# kijelz.net
KiCad netlist of a schematic drawn in EAGLE
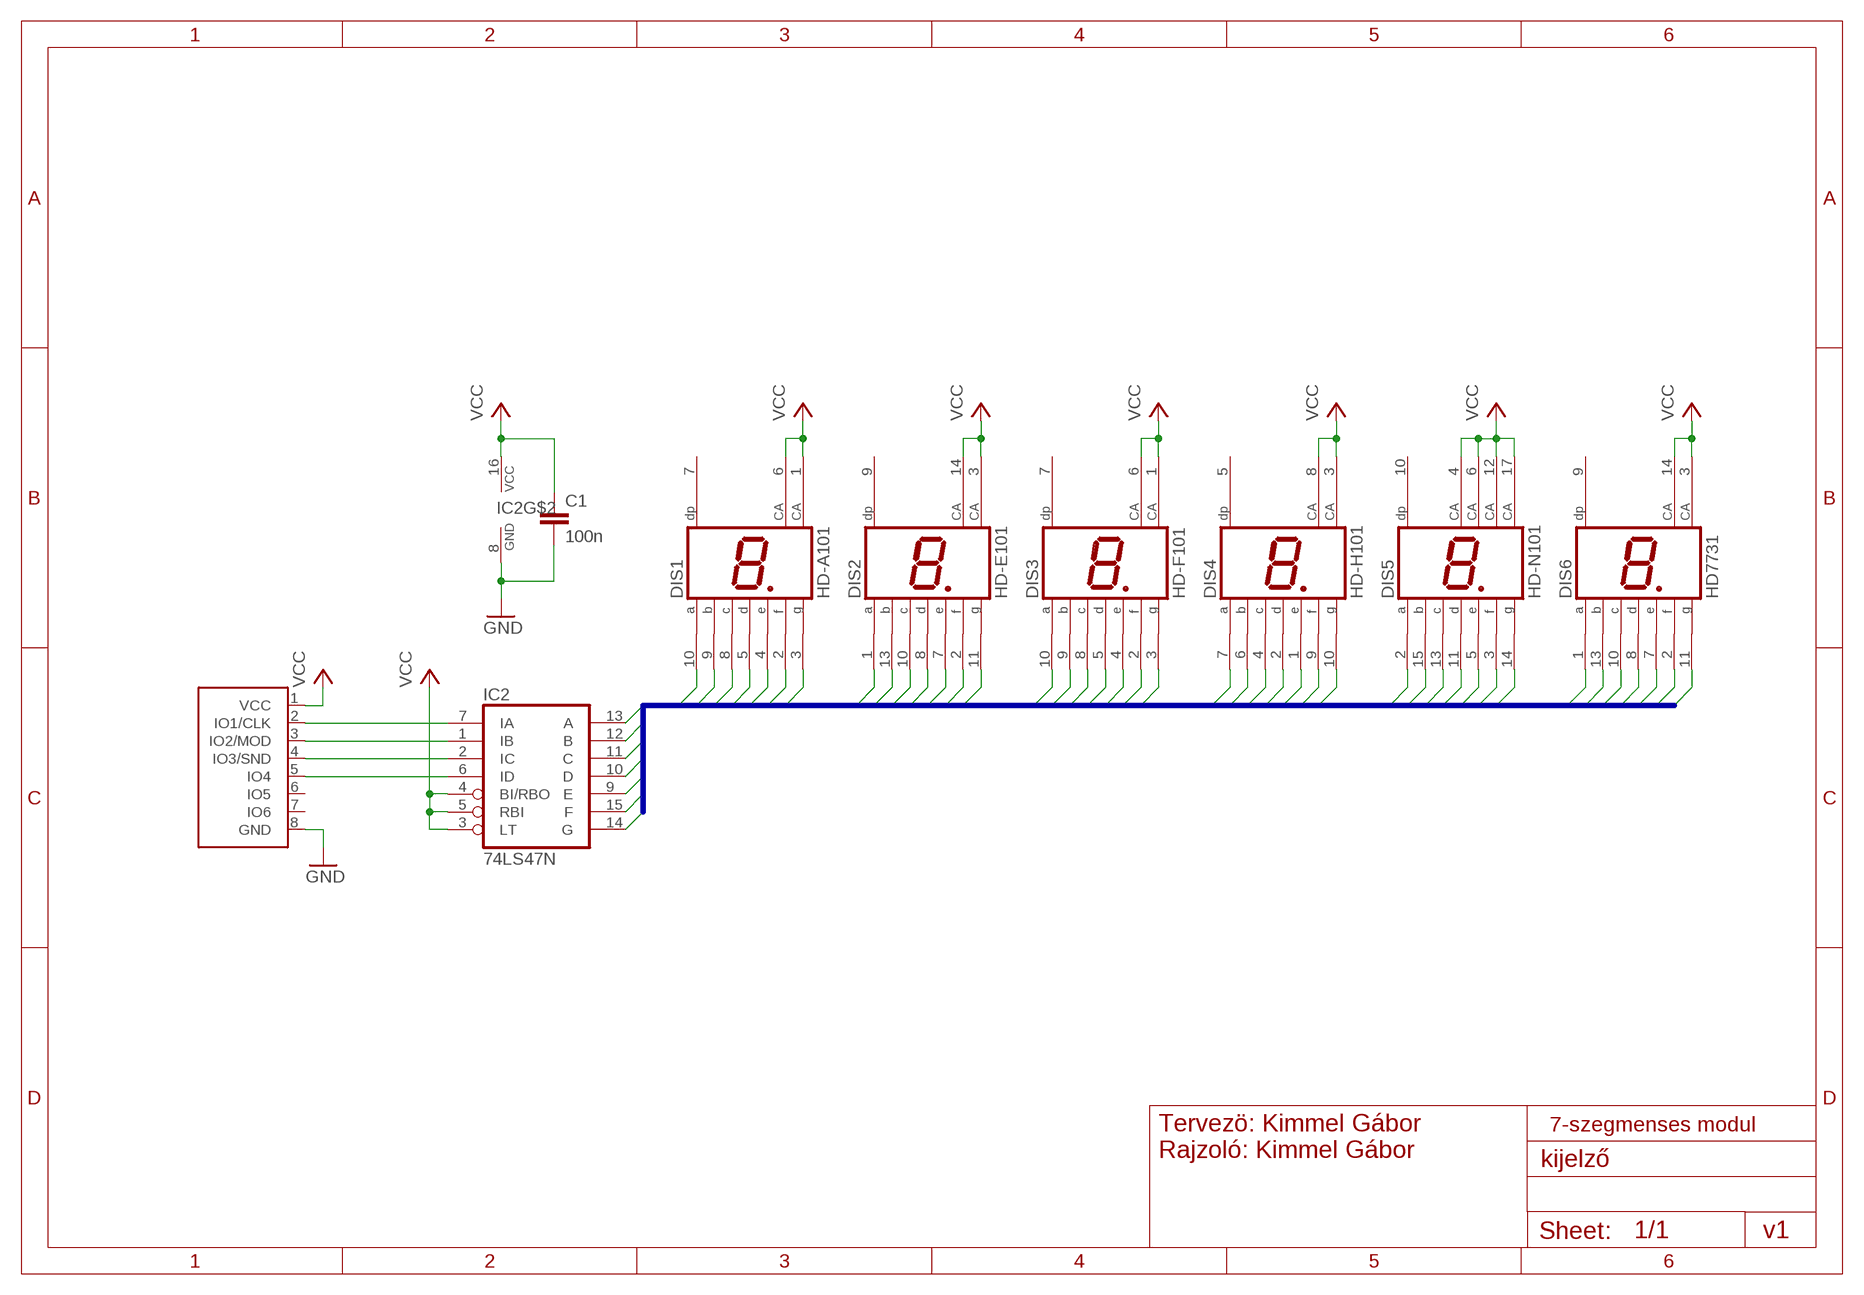
[diagram p0: schematic, sheet 1]

(export (version "E")
  (design (tool "Eeschema 10.0.6"))
  (components
    (comp (ref "C1")
      (value "100n")
      (footprint "eagle-import:C075-032X103")
      (libsource (lib "eagle-import") (part "C-EU075-032X103"))
    )
    (comp (ref "DIS1")
      (value "HD-A101")
      (footprint "eagle-import:HDSP-A")
      (libsource (lib "eagle-import") (part "HD-A101"))
    )
    (comp (ref "DIS2")
      (value "HD-E101")
      (footprint "eagle-import:HDSP-I")
      (libsource (lib "eagle-import") (part "HD-E101"))
    )
    (comp (ref "DIS3")
      (value "HD-F101")
      (footprint "eagle-import:HDSP-E")
      (libsource (lib "eagle-import") (part "HD-F101"))
    )
    (comp (ref "DIS4")
      (value "HD-H101")
      (footprint "eagle-import:HDSP-M")
      (libsource (lib "eagle-import") (part "HD-H101"))
    )
    (comp (ref "DIS5")
      (value "HD-N101")
      (footprint "eagle-import:HDSP-Q")
      (libsource (lib "eagle-import") (part "HD-N101"))
    )
    (comp (ref "DIS6")
      (value "HD7731")
      (footprint "eagle-import:HD7730")
      (libsource (lib "eagle-import") (part "HD7731"))
    )
    (comp (ref "IC2")
      (value "74LS47N")
      (footprint "eagle-import:DIL16")
      (libsource (lib "eagle-import") (part "7447NLS"))
    )
    (comp (ref "U$1")
      (value "GANZ-CONNECTOR")
      (footprint "eagle-import:FE08W")
      (libsource (lib "eagle-import") (part "GANZ-CONNECTOR"))
    )
  )
  (nets
    (net (code "1") (name "/A") (class "Default")
      (node (ref "DIS1") (pin "10") (pinfunction "A_10") (pintype "passive"))
      (node (ref "DIS2") (pin "1") (pinfunction "A_1") (pintype "passive"))
      (node (ref "DIS3") (pin "10") (pinfunction "A_10") (pintype "passive"))
      (node (ref "DIS4") (pin "7") (pinfunction "A_7") (pintype "passive"))
      (node (ref "DIS5") (pin "2") (pinfunction "A_2") (pintype "passive"))
      (node (ref "DIS6") (pin "1") (pinfunction "A_1") (pintype "passive"))
      (node (ref "IC2") (pin "13") (pinfunction "A_13") (pintype "output"))
    )
    (net (code "2") (name "/B") (class "Default")
      (node (ref "DIS1") (pin "9") (pinfunction "B_9") (pintype "passive"))
      (node (ref "DIS2") (pin "13") (pinfunction "B_13") (pintype "passive"))
      (node (ref "DIS3") (pin "9") (pinfunction "B_9") (pintype "passive"))
      (node (ref "DIS4") (pin "6") (pinfunction "B_6") (pintype "passive"))
      (node (ref "DIS5") (pin "15") (pinfunction "B_15") (pintype "passive"))
      (node (ref "DIS6") (pin "13") (pinfunction "B_13") (pintype "passive"))
      (node (ref "IC2") (pin "12") (pinfunction "B_12") (pintype "output"))
    )
    (net (code "3") (name "/C") (class "Default")
      (node (ref "DIS1") (pin "8") (pinfunction "C_8") (pintype "passive"))
      (node (ref "DIS2") (pin "10") (pinfunction "C_10") (pintype "passive"))
      (node (ref "DIS3") (pin "8") (pinfunction "C_8") (pintype "passive"))
      (node (ref "DIS4") (pin "4") (pinfunction "C_4") (pintype "passive"))
      (node (ref "DIS5") (pin "13") (pinfunction "C_13") (pintype "passive"))
      (node (ref "DIS6") (pin "10") (pinfunction "C_10") (pintype "passive"))
      (node (ref "IC2") (pin "11") (pinfunction "C_11") (pintype "output"))
    )
    (net (code "4") (name "/D") (class "Default")
      (node (ref "DIS1") (pin "5") (pinfunction "D_5") (pintype "passive"))
      (node (ref "DIS2") (pin "8") (pinfunction "D_8") (pintype "passive"))
      (node (ref "DIS3") (pin "5") (pinfunction "D_5") (pintype "passive"))
      (node (ref "DIS4") (pin "2") (pinfunction "D_2") (pintype "passive"))
      (node (ref "DIS5") (pin "11") (pinfunction "D_11") (pintype "passive"))
      (node (ref "DIS6") (pin "8") (pinfunction "D_8") (pintype "passive"))
      (node (ref "IC2") (pin "10") (pinfunction "D_10") (pintype "output"))
    )
    (net (code "5") (name "/E") (class "Default")
      (node (ref "DIS1") (pin "4") (pinfunction "E_4") (pintype "passive"))
      (node (ref "DIS2") (pin "7") (pinfunction "E_7") (pintype "passive"))
      (node (ref "DIS3") (pin "4") (pinfunction "E_4") (pintype "passive"))
      (node (ref "DIS4") (pin "1") (pinfunction "E_1") (pintype "passive"))
      (node (ref "DIS5") (pin "5") (pinfunction "E_5") (pintype "passive"))
      (node (ref "DIS6") (pin "7") (pinfunction "E_7") (pintype "passive"))
      (node (ref "IC2") (pin "9") (pinfunction "E_9") (pintype "output"))
    )
    (net (code "6") (name "/F") (class "Default")
      (node (ref "DIS1") (pin "2") (pinfunction "F_2") (pintype "passive"))
      (node (ref "DIS2") (pin "2") (pinfunction "F_2") (pintype "passive"))
      (node (ref "DIS3") (pin "2") (pinfunction "F_2") (pintype "passive"))
      (node (ref "DIS4") (pin "9") (pinfunction "F_9") (pintype "passive"))
      (node (ref "DIS5") (pin "3") (pinfunction "F_3") (pintype "passive"))
      (node (ref "DIS6") (pin "2") (pinfunction "F_2") (pintype "passive"))
      (node (ref "IC2") (pin "15") (pinfunction "F_15") (pintype "output"))
    )
    (net (code "7") (name "/G") (class "Default")
      (node (ref "DIS1") (pin "3") (pinfunction "G_3") (pintype "passive"))
      (node (ref "DIS2") (pin "11") (pinfunction "G_11") (pintype "passive"))
      (node (ref "DIS3") (pin "3") (pinfunction "G_3") (pintype "passive"))
      (node (ref "DIS4") (pin "10") (pinfunction "G_10") (pintype "passive"))
      (node (ref "DIS5") (pin "14") (pinfunction "G_14") (pintype "passive"))
      (node (ref "DIS6") (pin "11") (pinfunction "G_11") (pintype "passive"))
      (node (ref "IC2") (pin "14") (pinfunction "G_14") (pintype "output"))
    )
    (net (code "8") (name "GND") (class "Default")
      (node (ref "C1") (pin "2") (pinfunction "2_2") (pintype "passive"))
      (node (ref "IC2") (pin "8") (pinfunction "GND_8") (pintype "power_in"))
      (node (ref "U$1") (pin "8") (pinfunction "GND_8") (pintype "bidirectional"))
    )
    (net (code "9") (name "Net-(IC2A-IA)") (class "Default")
      (node (ref "IC2") (pin "7") (pinfunction "IA_7") (pintype "input"))
      (node (ref "U$1") (pin "2") (pinfunction "IO1/CLK_2") (pintype "bidirectional"))
    )
    (net (code "10") (name "Net-(IC2A-IB)") (class "Default")
      (node (ref "IC2") (pin "1") (pinfunction "IB_1") (pintype "input"))
      (node (ref "U$1") (pin "3") (pinfunction "IO2/MOD_3") (pintype "bidirectional"))
    )
    (net (code "11") (name "Net-(IC2A-IC)") (class "Default")
      (node (ref "IC2") (pin "2") (pinfunction "IC_2") (pintype "input"))
      (node (ref "U$1") (pin "4") (pinfunction "IO3/SND_4") (pintype "bidirectional"))
    )
    (net (code "12") (name "Net-(IC2A-ID)") (class "Default")
      (node (ref "IC2") (pin "6") (pinfunction "ID_6") (pintype "input"))
      (node (ref "U$1") (pin "5") (pinfunction "IO4_5") (pintype "bidirectional"))
    )
    (net (code "13") (name "VCC") (class "Default")
      (node (ref "C1") (pin "1") (pinfunction "1_1") (pintype "passive"))
      (node (ref "DIS1") (pin "1") (pinfunction "CA_1") (pintype "passive"))
      (node (ref "DIS1") (pin "6") (pinfunction "CA_6") (pintype "passive"))
      (node (ref "DIS2") (pin "14") (pinfunction "CA_14") (pintype "passive"))
      (node (ref "DIS2") (pin "3") (pinfunction "CA_3") (pintype "passive"))
      (node (ref "DIS3") (pin "1") (pinfunction "CA_1") (pintype "passive"))
      (node (ref "DIS3") (pin "6") (pinfunction "CA_6") (pintype "passive"))
      (node (ref "DIS4") (pin "3") (pinfunction "CA_3") (pintype "passive"))
      (node (ref "DIS4") (pin "8") (pinfunction "CA_8") (pintype "passive"))
      (node (ref "DIS5") (pin "12") (pinfunction "CA_12") (pintype "passive"))
      (node (ref "DIS5") (pin "17") (pinfunction "CA_17") (pintype "passive"))
      (node (ref "DIS5") (pin "4") (pinfunction "CA_4") (pintype "passive"))
      (node (ref "DIS5") (pin "6") (pinfunction "CA_6") (pintype "passive"))
      (node (ref "DIS6") (pin "14") (pinfunction "CA_14") (pintype "passive"))
      (node (ref "DIS6") (pin "3") (pinfunction "CA_3") (pintype "passive"))
      (node (ref "IC2") (pin "16") (pinfunction "VCC_16") (pintype "power_in"))
      (node (ref "IC2") (pin "3") (pinfunction "LT_3") (pintype "input"))
      (node (ref "IC2") (pin "4") (pinfunction "BI/RBO_4") (pintype "input"))
      (node (ref "IC2") (pin "5") (pinfunction "RBI_5") (pintype "input"))
      (node (ref "U$1") (pin "1") (pinfunction "VCC_1") (pintype "bidirectional"))
    )
    (net (code "14") (name "unconnected-(DIS1-DP-Pad7)") (class "Default")
      (node (ref "DIS1") (pin "7") (pinfunction "DP_7") (pintype "passive"))
    )
    (net (code "15") (name "unconnected-(DIS2-DP-Pad9)") (class "Default")
      (node (ref "DIS2") (pin "9") (pinfunction "DP_9") (pintype "passive"))
    )
    (net (code "16") (name "unconnected-(DIS3-DP-Pad7)") (class "Default")
      (node (ref "DIS3") (pin "7") (pinfunction "DP_7") (pintype "passive"))
    )
    (net (code "17") (name "unconnected-(DIS4-DP-Pad5)") (class "Default")
      (node (ref "DIS4") (pin "5") (pinfunction "DP_5") (pintype "passive"))
    )
    (net (code "18") (name "unconnected-(DIS5-DP-Pad10)") (class "Default")
      (node (ref "DIS5") (pin "10") (pinfunction "DP_10") (pintype "passive"))
    )
    (net (code "19") (name "unconnected-(DIS6-DP-Pad9)") (class "Default")
      (node (ref "DIS6") (pin "9") (pinfunction "DP_9") (pintype "passive"))
    )
    (net (code "20") (name "unconnected-(U$1-IO5-Pad6)") (class "Default")
      (node (ref "U$1") (pin "6") (pinfunction "IO5_6") (pintype "bidirectional"))
    )
    (net (code "21") (name "unconnected-(U$1-IO6-Pad7)") (class "Default")
      (node (ref "U$1") (pin "7") (pinfunction "IO6_7") (pintype "bidirectional"))
    )
  )
)
